# container-schematic.net
KiCad netlist of a schematic drawn in EAGLE
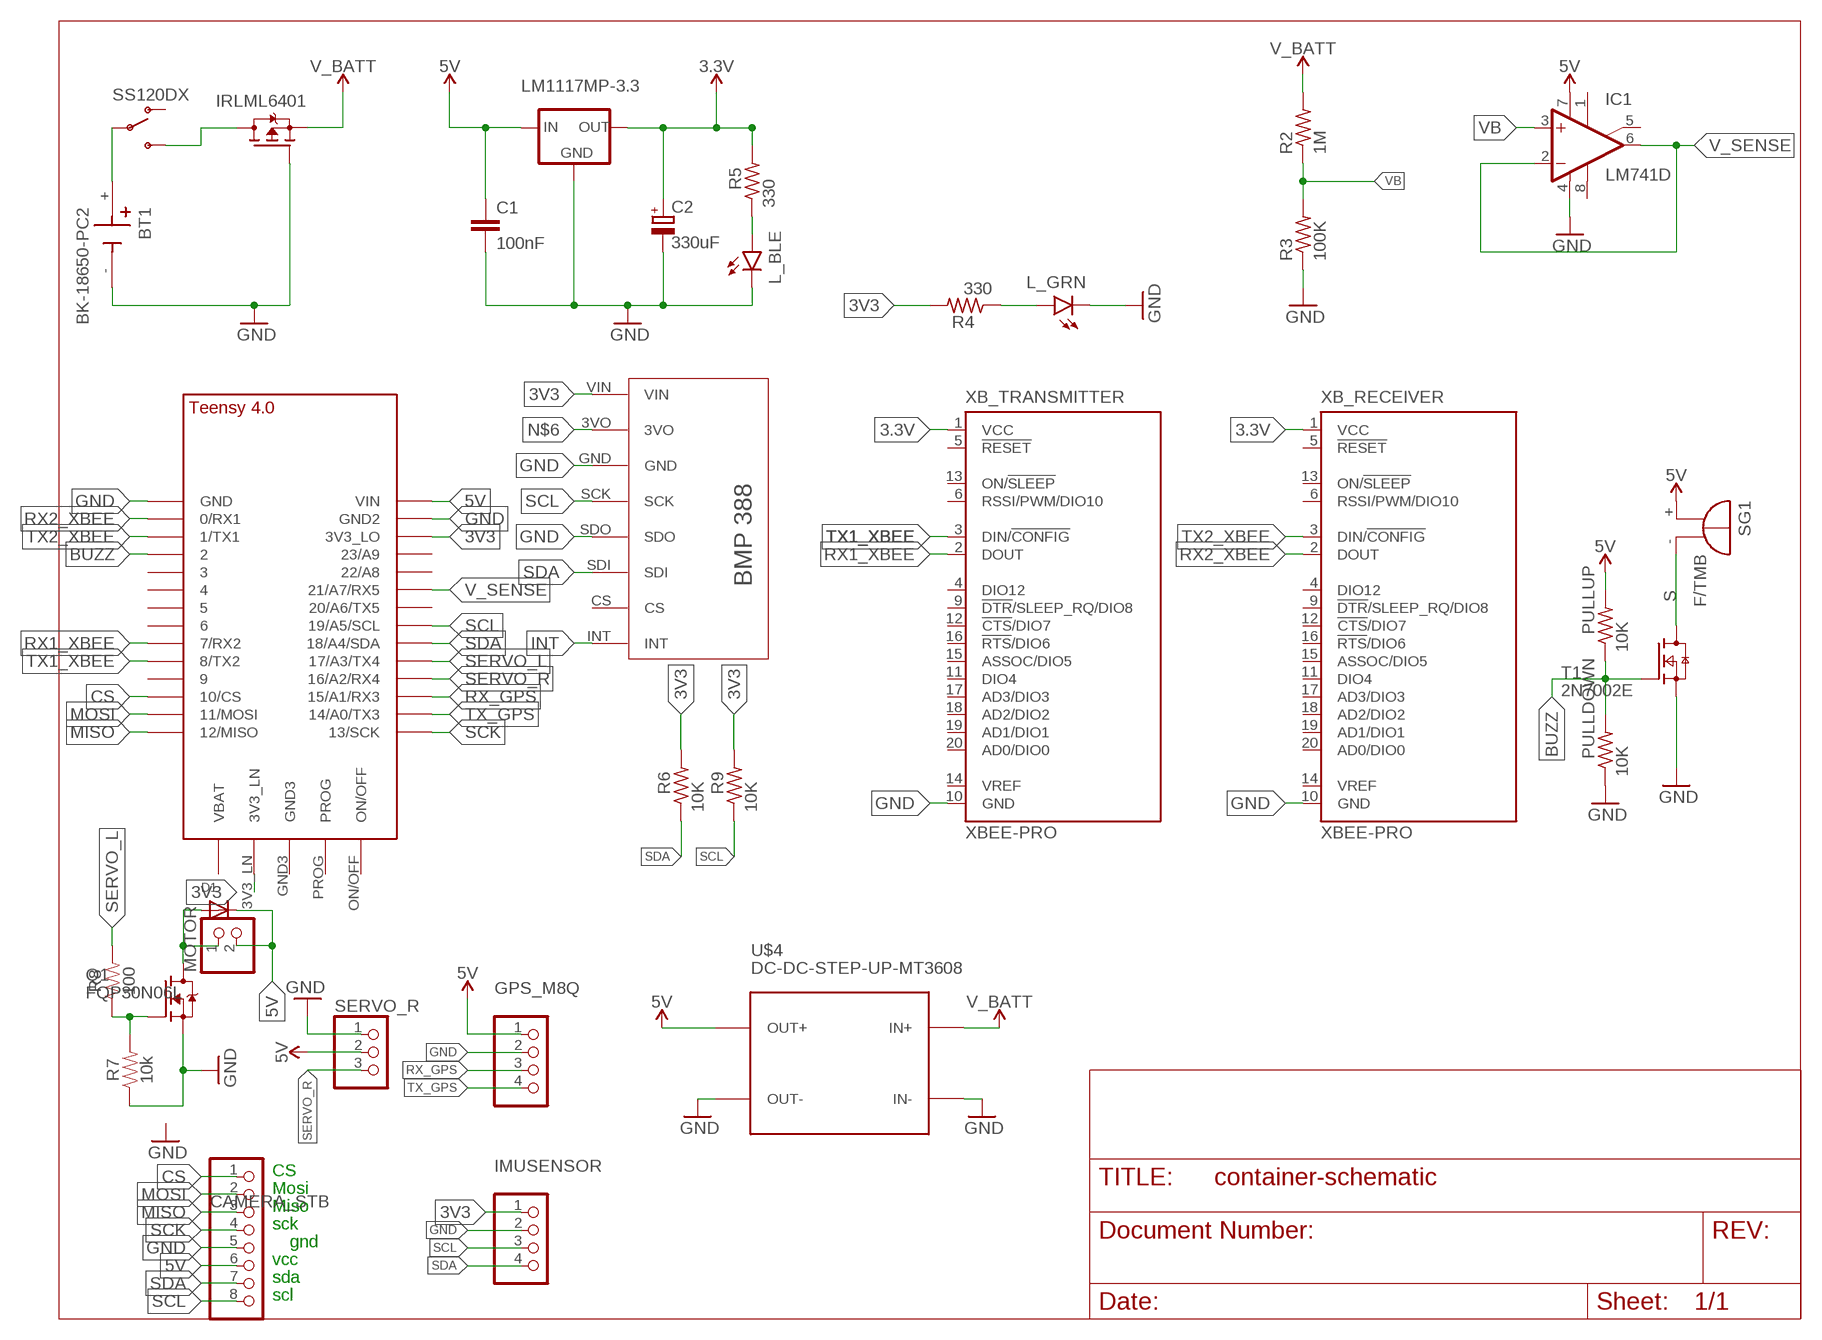
[diagram p0: schematic, sheet 1]

(export (version "E")
  (design (tool "Eeschema 10.0.6"))
  (components
    (comp (ref "BT1")
      (value "BK-18650-PC2")
      (footprint "eagle-import:BAT_BK-18650-PC2")
      (fields (field (name "MF") "MPD (Memory Protection Devices)"))
      (libsource (lib "eagle-import") (part "BK-18650-PC2"))
    )
    (comp (ref "C1")
      (value "100nF")
      (footprint "eagle-import:C0805")
      (libsource (lib "eagle-import") (part "C-EUC0805"))
    )
    (comp (ref "C2")
      (value "330uF")
      (footprint "eagle-import:D_7343-31W")
      (libsource (lib "eagle-import") (part "CPOL-EUD/7343-31W"))
    )
    (comp (ref "CAMERA_STB")
      (value "PINHD-1X8")
      (footprint "eagle-import:1X08")
      (libsource (lib "eagle-import") (part "PINHD-1X8"))
    )
    (comp (ref "D1")
      (value "DIODEDO-1N4148")
      (footprint "eagle-import:DO-1N4148")
      (libsource (lib "eagle-import") (part "DIODEDO-1N4148"))
    )
    (comp (ref "GPS_M8Q")
      (value "PINHD-1X4")
      (footprint "eagle-import:1X04")
      (libsource (lib "eagle-import") (part "PINHD-1X4"))
    )
    (comp (ref "IC1")
      (value "LM741D")
      (footprint "eagle-import:SO08")
      (libsource (lib "eagle-import") (part "741DLM"))
    )
    (comp (ref "IC2")
      (value "LM1117MP-3.3")
      (footprint "eagle-import:SOT223")
      (fields (field (name "MF") "Texas Instruments"))
      (libsource (lib "eagle-import") (part "LM1117?-MP3.3"))
    )
    (comp (ref "IMUSENSOR")
      (value "PINHD-1X4")
      (footprint "eagle-import:1X04")
      (libsource (lib "eagle-import") (part "PINHD-1X4"))
    )
    (comp (ref "IRLML6401")
      (value "MOSFET-PWIDE")
      (footprint "eagle-import:SOT23-WIDE")
      (libsource (lib "eagle-import") (part "MOSFET-PWIDE"))
    )
    (comp (ref "L_BLE")
      (value "LED1206")
      (footprint "eagle-import:LED-1206")
      (libsource (lib "eagle-import") (part "LED1206"))
    )
    (comp (ref "L_GRN")
      (value "LED1206")
      (footprint "eagle-import:LED-1206")
      (libsource (lib "eagle-import") (part "LED1206"))
    )
    (comp (ref "MOTOR")
      (value "PINHD-1X2")
      (footprint "eagle-import:1X02")
      (libsource (lib "eagle-import") (part "PINHD-1X2"))
    )
    (comp (ref "PULLDOWN")
      (value "10K")
      (footprint "eagle-import:M0805")
      (libsource (lib "eagle-import") (part "R-US_M0805"))
    )
    (comp (ref "PULLUP")
      (value "10K")
      (footprint "eagle-import:M0805")
      (libsource (lib "eagle-import") (part "R-US_M0805"))
    )
    (comp (ref "Q1")
      (value "FQP30N06L")
      (footprint "eagle-import:TO220V")
      (fields (field (name "MF") "ON Semiconductor"))
      (libsource (lib "eagle-import") (part "FQP30N06L"))
    )
    (comp (ref "R2")
      (value "1M")
      (footprint "eagle-import:M1206")
      (libsource (lib "eagle-import") (part "R-US_M1206"))
    )
    (comp (ref "R3")
      (value "100K")
      (footprint "eagle-import:M1206")
      (libsource (lib "eagle-import") (part "R-US_M1206"))
    )
    (comp (ref "R4")
      (value "330")
      (footprint "eagle-import:M0805")
      (libsource (lib "eagle-import") (part "R-US_M0805"))
    )
    (comp (ref "R5")
      (value "330")
      (footprint "eagle-import:M0805")
      (libsource (lib "eagle-import") (part "R-US_M0805"))
    )
    (comp (ref "R6")
      (value "10K")
      (footprint "eagle-import:M0805")
      (libsource (lib "eagle-import") (part "R-US_M0805"))
    )
    (comp (ref "R7")
      (value "10k")
      (footprint "eagle-import:0805")
      (libsource (lib "eagle-import") (part "RESISTOR0805"))
    )
    (comp (ref "R8")
      (value "100")
      (footprint "eagle-import:0805")
      (libsource (lib "eagle-import") (part "RESISTOR0805"))
    )
    (comp (ref "R9")
      (value "10K")
      (footprint "eagle-import:M0805")
      (libsource (lib "eagle-import") (part "R-US_M0805"))
    )
    (comp (ref "SERVO_R")
      (value "PINHD-1X3")
      (footprint "eagle-import:1X03")
      (libsource (lib "eagle-import") (part "PINHD-1X3"))
    )
    (comp (ref "SG1")
      (value "F/TMB")
      (footprint "eagle-import:F_TMB")
      (libsource (lib "eagle-import") (part "F/TMB"))
    )
    (comp (ref "T1")
      (value "2N7002E")
      (footprint "eagle-import:SOT23")
      (libsource (lib "eagle-import") (part "2N7002E"))
    )
    (comp (ref "U$1")
      (value "TEENSY_4.0-BASIC")
      (footprint "eagle-import:TEENSY_4.0-BASIC")
      (libsource (lib "eagle-import") (part "TEENSY_4.0-BASIC"))
    )
    (comp (ref "U$2")
      (value "BMP388")
      (footprint "eagle-import:BMP388")
      (libsource (lib "eagle-import") (part "BMP388"))
    )
    (comp (ref "U$3")
      (value "SS120DX")
      (footprint "eagle-import:SS12D0X")
      (libsource (lib "eagle-import") (part "SS120DX"))
    )
    (comp (ref "U$4")
      (value "DC-DC-STEP-UP-MT3608")
      (footprint "eagle-import:DC-DC-STEP-UP-MT3608")
      (libsource (lib "eagle-import") (part "DC-DC-STEP-UP-MT3608"))
    )
    (comp (ref "XB_RECEIVER")
      (value "XBEE-PRO")
      (footprint "eagle-import:XBEE-PRO")
      (fields (field (name "MPN") "XBP24-AWI-001"))
      (libsource (lib "eagle-import") (part "XBEE-PRO"))
    )
    (comp (ref "XB_TRANSMITTER")
      (value "XBEE-PRO")
      (footprint "eagle-import:XBEE-PRO")
      (fields (field (name "MPN") "XBP24-AWI-001"))
      (libsource (lib "eagle-import") (part "XBEE-PRO"))
    )
  )
  (nets
    (net (code "1") (name "/S") (class "Default")
      (node (ref "SG1") (pin "-") (pinfunction "-_-") (pintype "passive"))
      (node (ref "T1") (pin "3") (pinfunction "D_3") (pintype "passive"))
    )
    (net (code "2") (name "3.3V") (class "Default")
      (node (ref "C2") (pin "+") (pinfunction "+_+") (pintype "passive"))
      (node (ref "IC2") (pin "2") (pinfunction "OUT_2") (pintype "passive"))
      (node (ref "IC2") (pin "4") (pinfunction "OUT_4") (pintype "passive"))
      (node (ref "R5") (pin "2") (pinfunction "2_2") (pintype "passive"))
      (node (ref "XB_RECEIVER") (pin "1") (pinfunction "VCC_1") (pintype "power_in"))
      (node (ref "XB_TRANSMITTER") (pin "1") (pinfunction "VCC_1") (pintype "power_in"))
    )
    (net (code "3") (name "3V3") (class "Default")
      (node (ref "IMUSENSOR") (pin "1") (pinfunction "1_1") (pintype "passive"))
      (node (ref "R4") (pin "2") (pinfunction "2_2") (pintype "passive"))
      (node (ref "R6") (pin "2") (pinfunction "2_2") (pintype "passive"))
      (node (ref "R9") (pin "2") (pinfunction "2_2") (pintype "passive"))
      (node (ref "U$1") (pin "3V3_LN") (pinfunction "3V3_LN_3V3_LN") (pintype "bidirectional"))
      (node (ref "U$1") (pin "3V3_LO") (pinfunction "3V3_LO_3V3_LO") (pintype "bidirectional"))
      (node (ref "U$2") (pin "VIN") (pinfunction "VIN_VIN") (pintype "bidirectional"))
    )
    (net (code "4") (name "5V") (class "Default")
      (node (ref "C1") (pin "1") (pinfunction "1_1") (pintype "passive"))
      (node (ref "CAMERA_STB") (pin "6") (pinfunction "6_6") (pintype "passive"))
      (node (ref "D1") (pin "C") (pinfunction "C_C") (pintype "passive"))
      (node (ref "GPS_M8Q") (pin "1") (pinfunction "1_1") (pintype "passive"))
      (node (ref "IC1") (pin "7") (pinfunction "V+_7") (pintype "power_in"))
      (node (ref "IC2") (pin "3") (pinfunction "IN_3") (pintype "input"))
      (node (ref "MOTOR") (pin "2") (pinfunction "2_2") (pintype "passive"))
      (node (ref "PULLUP") (pin "2") (pinfunction "2_2") (pintype "passive"))
      (node (ref "SERVO_R") (pin "2") (pinfunction "2_2") (pintype "passive"))
      (node (ref "SG1") (pin "+") (pinfunction "+_+") (pintype "passive"))
      (node (ref "U$1") (pin "VIN") (pinfunction "VIN_VIN") (pintype "bidirectional"))
      (node (ref "U$4") (pin "OUT+") (pinfunction "OUT+_OUT+") (pintype "bidirectional"))
    )
    (net (code "5") (name "BUZZ") (class "Default")
      (node (ref "PULLDOWN") (pin "2") (pinfunction "2_2") (pintype "passive"))
      (node (ref "PULLUP") (pin "1") (pinfunction "1_1") (pintype "passive"))
      (node (ref "T1") (pin "1") (pinfunction "G_1") (pintype "passive"))
      (node (ref "U$1") (pin "2") (pinfunction "2_2") (pintype "bidirectional"))
    )
    (net (code "6") (name "CS") (class "Default")
      (node (ref "CAMERA_STB") (pin "1") (pinfunction "1_1") (pintype "passive"))
      (node (ref "U$1") (pin "10/CS") (pinfunction "10/CS_10/CS") (pintype "bidirectional"))
    )
    (net (code "7") (name "GND") (class "Default")
      (node (ref "BT1") (pin "-") (pinfunction "-_-") (pintype "passive"))
      (node (ref "C1") (pin "2") (pinfunction "2_2") (pintype "passive"))
      (node (ref "C2") (pin "-") (pinfunction "-_-") (pintype "passive"))
      (node (ref "CAMERA_STB") (pin "5") (pinfunction "5_5") (pintype "passive"))
      (node (ref "GPS_M8Q") (pin "2") (pinfunction "2_2") (pintype "passive"))
      (node (ref "IC1") (pin "4") (pinfunction "V-_4") (pintype "power_in"))
      (node (ref "IC2") (pin "1") (pinfunction "GND_1") (pintype "input"))
      (node (ref "IMUSENSOR") (pin "2") (pinfunction "2_2") (pintype "passive"))
      (node (ref "IRLML6401") (pin "1") (pinfunction "G_1") (pintype "passive"))
      (node (ref "L_BLE") (pin "C") (pinfunction "C_C") (pintype "passive"))
      (node (ref "L_GRN") (pin "C") (pinfunction "C_C") (pintype "passive"))
      (node (ref "PULLDOWN") (pin "1") (pinfunction "1_1") (pintype "passive"))
      (node (ref "Q1") (pin "3") (pinfunction "S_3") (pintype "passive"))
      (node (ref "R3") (pin "1") (pinfunction "1_1") (pintype "passive"))
      (node (ref "R7") (pin "1") (pinfunction "1_1") (pintype "passive"))
      (node (ref "SERVO_R") (pin "1") (pinfunction "1_1") (pintype "passive"))
      (node (ref "T1") (pin "2") (pinfunction "S_2") (pintype "passive"))
      (node (ref "U$1") (pin "GND") (pinfunction "GND_GND") (pintype "bidirectional"))
      (node (ref "U$1") (pin "GND2") (pinfunction "GND2_GND2") (pintype "bidirectional"))
      (node (ref "U$2") (pin "GND") (pinfunction "GND_GND") (pintype "bidirectional"))
      (node (ref "U$2") (pin "SDO") (pinfunction "SDO_SDO") (pintype "bidirectional"))
      (node (ref "U$4") (pin "IN-") (pinfunction "IN-_IN-") (pintype "bidirectional"))
      (node (ref "U$4") (pin "OUT-") (pinfunction "OUT-_OUT-") (pintype "bidirectional"))
      (node (ref "XB_RECEIVER") (pin "10") (pinfunction "GND_10") (pintype "power_in"))
      (node (ref "XB_TRANSMITTER") (pin "10") (pinfunction "GND_10") (pintype "power_in"))
    )
    (net (code "8") (name "INT") (class "Default")
      (node (ref "U$2") (pin "INT") (pinfunction "INT_INT") (pintype "bidirectional"))
    )
    (net (code "9") (name "MISO") (class "Default")
      (node (ref "CAMERA_STB") (pin "3") (pinfunction "3_3") (pintype "passive"))
      (node (ref "U$1") (pin "12/MISO") (pinfunction "12/MISO_12/MISO") (pintype "bidirectional"))
    )
    (net (code "10") (name "MOSI") (class "Default")
      (node (ref "CAMERA_STB") (pin "2") (pinfunction "2_2") (pintype "passive"))
      (node (ref "U$1") (pin "11/MOSI") (pinfunction "11/MOSI_11/MOSI") (pintype "bidirectional"))
    )
    (net (code "11") (name "N$6") (class "Default")
      (node (ref "U$2") (pin "3VO") (pinfunction "3VO_3VO") (pintype "bidirectional"))
    )
    (net (code "12") (name "Net-(BT1-Pad+)") (class "Default")
      (node (ref "BT1") (pin "+") (pinfunction "+_+") (pintype "passive"))
      (node (ref "U$3") (pin "2") (pinfunction "2_2") (pintype "passive"))
    )
    (net (code "13") (name "Net-(IRLML6401-D)") (class "Default")
      (node (ref "IRLML6401") (pin "3") (pinfunction "D_3") (pintype "passive"))
      (node (ref "U$3") (pin "3") (pinfunction "3_3") (pintype "passive"))
    )
    (net (code "14") (name "Net-(L_BLE-PadA)") (class "Default")
      (node (ref "L_BLE") (pin "A") (pinfunction "A_A") (pintype "passive"))
      (node (ref "R5") (pin "1") (pinfunction "1_1") (pintype "passive"))
    )
    (net (code "15") (name "Net-(L_GRN-PadA)") (class "Default")
      (node (ref "L_GRN") (pin "A") (pinfunction "A_A") (pintype "passive"))
      (node (ref "R4") (pin "1") (pinfunction "1_1") (pintype "passive"))
    )
    (net (code "16") (name "Net-(Q1-D)") (class "Default")
      (node (ref "D1") (pin "A") (pinfunction "A_A") (pintype "passive"))
      (node (ref "MOTOR") (pin "1") (pinfunction "1_1") (pintype "passive"))
      (node (ref "Q1") (pin "2") (pinfunction "D_2") (pintype "passive"))
    )
    (net (code "17") (name "Net-(Q1-G)") (class "Default")
      (node (ref "Q1") (pin "1") (pinfunction "G_1") (pintype "passive"))
      (node (ref "R7") (pin "2") (pinfunction "2_2") (pintype "passive"))
      (node (ref "R8") (pin "1") (pinfunction "1_1") (pintype "passive"))
    )
    (net (code "18") (name "RX1_XBEE") (class "Default")
      (node (ref "U$1") (pin "7") (pinfunction "7/RX2_7") (pintype "bidirectional"))
      (node (ref "XB_TRANSMITTER") (pin "2") (pinfunction "DOUT_2") (pintype "output"))
    )
    (net (code "19") (name "RX2_XBEE") (class "Default")
      (node (ref "U$1") (pin "0/RX") (pinfunction "0/RX1_0/RX") (pintype "bidirectional"))
      (node (ref "XB_RECEIVER") (pin "2") (pinfunction "DOUT_2") (pintype "output"))
    )
    (net (code "20") (name "RX_GPS") (class "Default")
      (node (ref "GPS_M8Q") (pin "3") (pinfunction "3_3") (pintype "passive"))
      (node (ref "U$1") (pin "15/A1") (pinfunction "15/A1/RX3_15/A1") (pintype "bidirectional"))
    )
    (net (code "21") (name "SCK") (class "Default")
      (node (ref "CAMERA_STB") (pin "4") (pinfunction "4_4") (pintype "passive"))
      (node (ref "U$1") (pin "13/SCK") (pinfunction "13/SCK_13/SCK") (pintype "bidirectional"))
    )
    (net (code "22") (name "SCL") (class "Default")
      (node (ref "CAMERA_STB") (pin "8") (pinfunction "8_8") (pintype "passive"))
      (node (ref "IMUSENSOR") (pin "3") (pinfunction "3_3") (pintype "passive"))
      (node (ref "R9") (pin "1") (pinfunction "1_1") (pintype "passive"))
      (node (ref "U$1") (pin "19/A5/SCL") (pinfunction "19/A5/SCL_19/A5/SCL") (pintype "bidirectional"))
      (node (ref "U$2") (pin "SCK") (pinfunction "SCK_SCK") (pintype "bidirectional"))
    )
    (net (code "23") (name "SDA") (class "Default")
      (node (ref "CAMERA_STB") (pin "7") (pinfunction "7_7") (pintype "passive"))
      (node (ref "IMUSENSOR") (pin "4") (pinfunction "4_4") (pintype "passive"))
      (node (ref "R6") (pin "1") (pinfunction "1_1") (pintype "passive"))
      (node (ref "U$1") (pin "18/A4/SDA") (pinfunction "18/A4/SDA_18/A4/SDA") (pintype "bidirectional"))
      (node (ref "U$2") (pin "SDI") (pinfunction "SDI_SDI") (pintype "bidirectional"))
    )
    (net (code "24") (name "SERVO_L") (class "Default")
      (node (ref "R8") (pin "2") (pinfunction "2_2") (pintype "passive"))
      (node (ref "U$1") (pin "17/A3") (pinfunction "17/A3/TX4_17/A3") (pintype "bidirectional"))
    )
    (net (code "25") (name "SERVO_R") (class "Default")
      (node (ref "SERVO_R") (pin "3") (pinfunction "3_3") (pintype "passive"))
      (node (ref "U$1") (pin "16/A2") (pinfunction "16/A2/RX4_16/A2") (pintype "bidirectional"))
    )
    (net (code "26") (name "TX1_XBEE") (class "Default")
      (node (ref "U$1") (pin "8") (pinfunction "8/TX2_8") (pintype "bidirectional"))
      (node (ref "XB_TRANSMITTER") (pin "3") (pinfunction "DIN/~{CONFIG}_3") (pintype "input"))
    )
    (net (code "27") (name "TX2_XBEE") (class "Default")
      (node (ref "U$1") (pin "1/TX") (pinfunction "1/TX1_1/TX") (pintype "bidirectional"))
      (node (ref "XB_RECEIVER") (pin "3") (pinfunction "DIN/~{CONFIG}_3") (pintype "input"))
    )
    (net (code "28") (name "TX_GPS") (class "Default")
      (node (ref "GPS_M8Q") (pin "4") (pinfunction "4_4") (pintype "passive"))
      (node (ref "U$1") (pin "14/A0") (pinfunction "14/A0/TX3_14/A0") (pintype "bidirectional"))
    )
    (net (code "29") (name "VB") (class "Default")
      (node (ref "IC1") (pin "3") (pinfunction "+IN_3") (pintype "input"))
      (node (ref "R2") (pin "1") (pinfunction "1_1") (pintype "passive"))
      (node (ref "R3") (pin "2") (pinfunction "2_2") (pintype "passive"))
    )
    (net (code "30") (name "V_BATT") (class "Default")
      (node (ref "IRLML6401") (pin "2") (pinfunction "S_2") (pintype "passive"))
      (node (ref "R2") (pin "2") (pinfunction "2_2") (pintype "passive"))
      (node (ref "U$4") (pin "IN+") (pinfunction "IN+_IN+") (pintype "bidirectional"))
    )
    (net (code "31") (name "V_SENSE") (class "Default")
      (node (ref "IC1") (pin "2") (pinfunction "-IN_2") (pintype "input"))
      (node (ref "IC1") (pin "6") (pinfunction "OUT_6") (pintype "output"))
      (node (ref "U$1") (pin "21/A7") (pinfunction "21/A7/RX5_21/A7") (pintype "bidirectional"))
    )
    (net (code "32") (name "unconnected-(IC1-ON1-Pad1)") (class "Default")
      (node (ref "IC1") (pin "1") (pinfunction "ON1_1") (pintype "passive"))
    )
    (net (code "33") (name "unconnected-(IC1-ON2-Pad5)") (class "Default")
      (node (ref "IC1") (pin "5") (pinfunction "ON2_5") (pintype "passive"))
    )
    (net (code "34") (name "unconnected-(IC1-OPT-Pad8)") (class "Default")
      (node (ref "IC1") (pin "8") (pinfunction "OPT_8") (pintype "passive"))
    )
    (net (code "35") (name "unconnected-(U$1-3-Pad3{slash}CANTX)") (class "Default")
      (node (ref "U$1") (pin "3/CANTX") (pinfunction "3_3/CANTX") (pintype "bidirectional"))
    )
    (net (code "36") (name "unconnected-(U$1-4-Pad4{slash}CANRX)") (class "Default")
      (node (ref "U$1") (pin "4/CANRX") (pinfunction "4_4/CANRX") (pintype "bidirectional"))
    )
    (net (code "37") (name "unconnected-(U$1-9-Pad9{slash}CS)") (class "Default")
      (node (ref "U$1") (pin "9/CS") (pinfunction "9_9/CS") (pintype "bidirectional"))
    )
    (net (code "38") (name "unconnected-(U$1-20{slash}A6{slash}TX5-Pad20{slash}A6)") (class "Default")
      (node (ref "U$1") (pin "20/A6") (pinfunction "20/A6/TX5_20/A6") (pintype "bidirectional"))
    )
    (net (code "39") (name "unconnected-(U$1-Pad5)") (class "Default")
      (node (ref "U$1") (pin "5") (pinfunction "5_5") (pintype "bidirectional"))
    )
    (net (code "40") (name "unconnected-(U$1-Pad6)") (class "Default")
      (node (ref "U$1") (pin "6") (pinfunction "6_6") (pintype "bidirectional"))
    )
    (net (code "41") (name "unconnected-(U$1-Pad22{slash}A8)") (class "Default")
      (node (ref "U$1") (pin "22/A8") (pinfunction "22/A8_22/A8") (pintype "bidirectional"))
    )
    (net (code "42") (name "unconnected-(U$1-Pad23{slash}A9)") (class "Default")
      (node (ref "U$1") (pin "23/A9") (pinfunction "23/A9_23/A9") (pintype "bidirectional"))
    )
    (net (code "43") (name "unconnected-(U$1-PadGND3)") (class "Default")
      (node (ref "U$1") (pin "GND3") (pinfunction "GND3_GND3") (pintype "bidirectional"))
    )
    (net (code "44") (name "unconnected-(U$1-PadON{slash}OFF)") (class "Default")
      (node (ref "U$1") (pin "ON/OFF") (pinfunction "ON/OFF_ON/OFF") (pintype "bidirectional"))
    )
    (net (code "45") (name "unconnected-(U$1-PadPROG)") (class "Default")
      (node (ref "U$1") (pin "PROG") (pinfunction "PROG_PROG") (pintype "bidirectional"))
    )
    (net (code "46") (name "unconnected-(U$1-VBAT-PadVBAT\\)") (class "Default")
      (node (ref "U$1") (pin "VBAT\\") (pinfunction "VBAT_VBAT\\") (pintype "bidirectional"))
    )
    (net (code "47") (name "unconnected-(U$2-PadCS)") (class "Default")
      (node (ref "U$2") (pin "CS") (pinfunction "CS_CS") (pintype "bidirectional"))
    )
    (net (code "48") (name "unconnected-(U$3-Pad1)") (class "Default")
      (node (ref "U$3") (pin "1") (pinfunction "1_1") (pintype "passive"))
    )
    (net (code "49") (name "unconnected-(XB_RECEIVER-AD0{slash}DIO0-Pad20)") (class "Default")
      (node (ref "XB_RECEIVER") (pin "20") (pinfunction "AD0/DIO0_20") (pintype "bidirectional"))
    )
    (net (code "50") (name "unconnected-(XB_RECEIVER-AD1{slash}DIO1-Pad19)") (class "Default")
      (node (ref "XB_RECEIVER") (pin "19") (pinfunction "AD1/DIO1_19") (pintype "bidirectional"))
    )
    (net (code "51") (name "unconnected-(XB_RECEIVER-AD2{slash}DIO2-Pad18)") (class "Default")
      (node (ref "XB_RECEIVER") (pin "18") (pinfunction "AD2/DIO2_18") (pintype "bidirectional"))
    )
    (net (code "52") (name "unconnected-(XB_RECEIVER-AD3{slash}DIO3-Pad17)") (class "Default")
      (node (ref "XB_RECEIVER") (pin "17") (pinfunction "AD3/DIO3_17") (pintype "bidirectional"))
    )
    (net (code "53") (name "unconnected-(XB_RECEIVER-ASSOC{slash}DIO5-Pad15)") (class "Default")
      (node (ref "XB_RECEIVER") (pin "15") (pinfunction "ASSOC/DIO5_15") (pintype "bidirectional"))
    )
    (net (code "54") (name "unconnected-(XB_RECEIVER-DIO4-Pad11)") (class "Default")
      (node (ref "XB_RECEIVER") (pin "11") (pinfunction "DIO4_11") (pintype "bidirectional"))
    )
    (net (code "55") (name "unconnected-(XB_RECEIVER-DIO12-Pad4)") (class "Default")
      (node (ref "XB_RECEIVER") (pin "4") (pinfunction "DIO12_4") (pintype "bidirectional"))
    )
    (net (code "56") (name "unconnected-(XB_RECEIVER-ON{slash}~{SLEEP}-Pad13)") (class "Default")
      (node (ref "XB_RECEIVER") (pin "13") (pinfunction "ON/~{SLEEP}_13") (pintype "output"))
    )
    (net (code "57") (name "unconnected-(XB_RECEIVER-RSSI{slash}PWM{slash}DIO10-Pad6)") (class "Default")
      (node (ref "XB_RECEIVER") (pin "6") (pinfunction "RSSI/PWM/DIO10_6") (pintype "output"))
    )
    (net (code "58") (name "unconnected-(XB_RECEIVER-VREF-Pad14)") (class "Default")
      (node (ref "XB_RECEIVER") (pin "14") (pinfunction "VREF_14") (pintype "input"))
    )
    (net (code "59") (name "unconnected-(XB_RECEIVER-~{CTS}{slash}DIO7-Pad12)") (class "Default")
      (node (ref "XB_RECEIVER") (pin "12") (pinfunction "~{CTS}/DIO7_12") (pintype "bidirectional"))
    )
    (net (code "60") (name "unconnected-(XB_RECEIVER-~{DTR}{slash}SLEEP_RQ{slash}DIO8-Pad9)") (class "Default")
      (node (ref "XB_RECEIVER") (pin "9") (pinfunction "~{DTR}/SLEEP_RQ/DIO8_9") (pintype "bidirectional"))
    )
    (net (code "61") (name "unconnected-(XB_RECEIVER-~{RESET}-Pad5)") (class "Default")
      (node (ref "XB_RECEIVER") (pin "5") (pinfunction "~{RESET}_5") (pintype "input"))
    )
    (net (code "62") (name "unconnected-(XB_RECEIVER-~{RTS}{slash}DIO6-Pad16)") (class "Default")
      (node (ref "XB_RECEIVER") (pin "16") (pinfunction "~{RTS}/DIO6_16") (pintype "bidirectional"))
    )
    (net (code "63") (name "unconnected-(XB_TRANSMITTER-AD0{slash}DIO0-Pad20)") (class "Default")
      (node (ref "XB_TRANSMITTER") (pin "20") (pinfunction "AD0/DIO0_20") (pintype "bidirectional"))
    )
    (net (code "64") (name "unconnected-(XB_TRANSMITTER-AD1{slash}DIO1-Pad19)") (class "Default")
      (node (ref "XB_TRANSMITTER") (pin "19") (pinfunction "AD1/DIO1_19") (pintype "bidirectional"))
    )
    (net (code "65") (name "unconnected-(XB_TRANSMITTER-AD2{slash}DIO2-Pad18)") (class "Default")
      (node (ref "XB_TRANSMITTER") (pin "18") (pinfunction "AD2/DIO2_18") (pintype "bidirectional"))
    )
    (net (code "66") (name "unconnected-(XB_TRANSMITTER-AD3{slash}DIO3-Pad17)") (class "Default")
      (node (ref "XB_TRANSMITTER") (pin "17") (pinfunction "AD3/DIO3_17") (pintype "bidirectional"))
    )
    (net (code "67") (name "unconnected-(XB_TRANSMITTER-ASSOC{slash}DIO5-Pad15)") (class "Default")
      (node (ref "XB_TRANSMITTER") (pin "15") (pinfunction "ASSOC/DIO5_15") (pintype "bidirectional"))
    )
    (net (code "68") (name "unconnected-(XB_TRANSMITTER-DIO4-Pad11)") (class "Default")
      (node (ref "XB_TRANSMITTER") (pin "11") (pinfunction "DIO4_11") (pintype "bidirectional"))
    )
    (net (code "69") (name "unconnected-(XB_TRANSMITTER-DIO12-Pad4)") (class "Default")
      (node (ref "XB_TRANSMITTER") (pin "4") (pinfunction "DIO12_4") (pintype "bidirectional"))
    )
    (net (code "70") (name "unconnected-(XB_TRANSMITTER-ON{slash}~{SLEEP}-Pad13)") (class "Default")
      (node (ref "XB_TRANSMITTER") (pin "13") (pinfunction "ON/~{SLEEP}_13") (pintype "output"))
    )
    (net (code "71") (name "unconnected-(XB_TRANSMITTER-RSSI{slash}PWM{slash}DIO10-Pad6)") (class "Default")
      (node (ref "XB_TRANSMITTER") (pin "6") (pinfunction "RSSI/PWM/DIO10_6") (pintype "output"))
    )
    (net (code "72") (name "unconnected-(XB_TRANSMITTER-VREF-Pad14)") (class "Default")
      (node (ref "XB_TRANSMITTER") (pin "14") (pinfunction "VREF_14") (pintype "input"))
    )
    (net (code "73") (name "unconnected-(XB_TRANSMITTER-~{CTS}{slash}DIO7-Pad12)") (class "Default")
      (node (ref "XB_TRANSMITTER") (pin "12") (pinfunction "~{CTS}/DIO7_12") (pintype "bidirectional"))
    )
    (net (code "74") (name "unconnected-(XB_TRANSMITTER-~{DTR}{slash}SLEEP_RQ{slash}DIO8-Pad9)") (class "Default")
      (node (ref "XB_TRANSMITTER") (pin "9") (pinfunction "~{DTR}/SLEEP_RQ/DIO8_9") (pintype "bidirectional"))
    )
    (net (code "75") (name "unconnected-(XB_TRANSMITTER-~{RESET}-Pad5)") (class "Default")
      (node (ref "XB_TRANSMITTER") (pin "5") (pinfunction "~{RESET}_5") (pintype "input"))
    )
    (net (code "76") (name "unconnected-(XB_TRANSMITTER-~{RTS}{slash}DIO6-Pad16)") (class "Default")
      (node (ref "XB_TRANSMITTER") (pin "16") (pinfunction "~{RTS}/DIO6_16") (pintype "bidirectional"))
    )
  )
)
